# TrafficLight_ABCDEF.net
KiCad netlist of a schematic drawn in Altium Designer
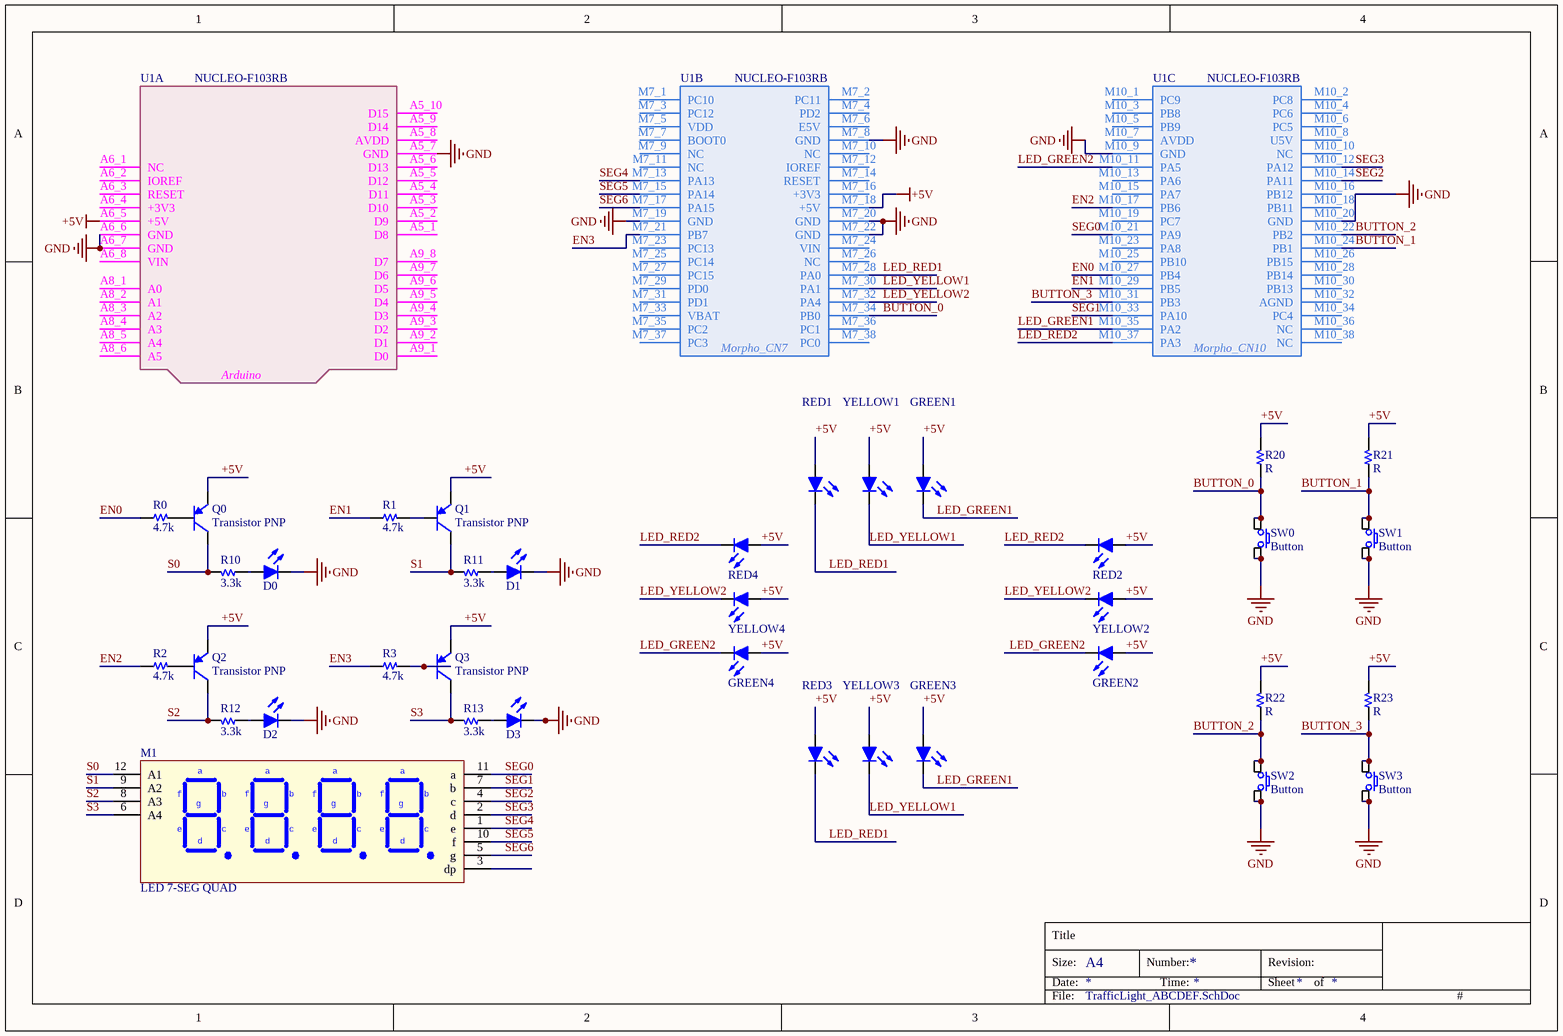
[diagram p0: TrafficLight_ABCDEF.SchDoc]

(export (version "E")
  (design (tool "Eeschema 10.0.6"))
  (components
    (comp (ref "D0")
      (value "Led")
      (footprint "Led 0603 - red")
      (description "Typical LED")
      (libsource (lib "led") (part "Led"))
    )
    (comp (ref "D1")
      (value "Led")
      (footprint "Led 0603 - red")
      (description "Typical LED")
      (libsource (lib "led") (part "Led"))
    )
    (comp (ref "D2")
      (value "Led")
      (footprint "Led 0603 - red")
      (description "Typical LED")
      (libsource (lib "led") (part "Led"))
    )
    (comp (ref "D3")
      (value "Led")
      (footprint "Led 0603 - red")
      (description "Typical LED")
      (libsource (lib "led") (part "Led"))
    )
    (comp (ref "GREEN1")
      (value "Led")
      (footprint "LED 5MM - GREEN")
      (description "Typical LED")
      (libsource (lib "led") (part "Led"))
    )
    (comp (ref "GREEN2")
      (value "Led")
      (footprint "LED 5MM - GREEN")
      (description "Typical LED")
      (libsource (lib "led") (part "Led"))
    )
    (comp (ref "GREEN3")
      (value "Led")
      (footprint "LED 5MM - GREEN")
      (description "Typical LED")
      (libsource (lib "led") (part "Led"))
    )
    (comp (ref "GREEN4")
      (value "Led")
      (footprint "LED 5MM - GREEN")
      (description "Typical LED")
      (libsource (lib "led") (part "Led"))
    )
    (comp (ref "M1")
      (value "LED 7-SEG QUAD")
      (footprint "LED/7SEG/0.56/QUAD")
      (description "LED 7-SEG 0.56 QUAD RED")
      (libsource (lib "led") (part "LED 7-SEG QUAD"))
    )
    (comp (ref "Q0")
      (value "Transistor PNP")
      (footprint "SOT-23")
      (description "PNP Bipolar Transistor")
      (libsource (lib "chipfc_libs") (part "Transistor PNP"))
    )
    (comp (ref "Q1")
      (value "Transistor PNP")
      (footprint "SOT-23")
      (description "PNP Bipolar Transistor")
      (libsource (lib "chipfc_libs") (part "Transistor PNP"))
    )
    (comp (ref "Q2")
      (value "Transistor PNP")
      (footprint "SOT-23")
      (description "PNP Bipolar Transistor")
      (libsource (lib "chipfc_libs") (part "Transistor PNP"))
    )
    (comp (ref "Q3")
      (value "Transistor PNP")
      (footprint "SOT-23")
      (description "PNP Bipolar Transistor")
      (libsource (lib "chipfc_libs") (part "Transistor PNP"))
    )
    (comp (ref "R0")
      (value "4.7k")
      (footprint "R 0805")
      (description "Resistor")
      (libsource (lib "chipfc_libs") (part "Resistor"))
    )
    (comp (ref "R1")
      (value "4.7k")
      (footprint "R 0805")
      (description "Resistor")
      (libsource (lib "chipfc_libs") (part "Resistor"))
    )
    (comp (ref "R2")
      (value "4.7k")
      (footprint "R 0805")
      (description "Resistor")
      (libsource (lib "chipfc_libs") (part "Resistor"))
    )
    (comp (ref "R3")
      (value "4.7k")
      (footprint "R 0805")
      (description "Resistor")
      (libsource (lib "chipfc_libs") (part "Resistor"))
    )
    (comp (ref "R10")
      (value "3.3k")
      (footprint "R 0805")
      (description "Resistor")
      (libsource (lib "chipfc_libs") (part "Resistor"))
    )
    (comp (ref "R11")
      (value "3.3k")
      (footprint "R 0805")
      (description "Resistor")
      (libsource (lib "chipfc_libs") (part "Resistor"))
    )
    (comp (ref "R12")
      (value "3.3k")
      (footprint "R 0805")
      (description "Resistor")
      (libsource (lib "chipfc_libs") (part "Resistor"))
    )
    (comp (ref "R13")
      (value "3.3k")
      (footprint "R 0805")
      (description "Resistor")
      (libsource (lib "chipfc_libs") (part "Resistor"))
    )
    (comp (ref "R20")
      (value "R")
      (footprint "R 0805")
      (description "Resistor")
      (libsource (lib "chipfc_libs") (part "Resistor"))
    )
    (comp (ref "R21")
      (value "R")
      (footprint "R 0805")
      (description "Resistor")
      (libsource (lib "chipfc_libs") (part "Resistor"))
    )
    (comp (ref "R22")
      (value "R")
      (footprint "R 0805")
      (description "Resistor")
      (libsource (lib "chipfc_libs") (part "Resistor"))
    )
    (comp (ref "R23")
      (value "R")
      (footprint "R 0805")
      (description "Resistor")
      (libsource (lib "chipfc_libs") (part "Resistor"))
    )
    (comp (ref "RED1")
      (value "Led")
      (footprint "LED 3MM - red")
      (description "Typical LED")
      (libsource (lib "led") (part "Led"))
    )
    (comp (ref "RED2")
      (value "Led")
      (footprint "LED 3MM - red")
      (description "Typical LED")
      (libsource (lib "led") (part "Led"))
    )
    (comp (ref "RED3")
      (value "Led")
      (footprint "LED 3MM - red")
      (description "Typical LED")
      (libsource (lib "led") (part "Led"))
    )
    (comp (ref "RED4")
      (value "Led")
      (footprint "LED 3MM - red")
      (description "Typical LED")
      (libsource (lib "led") (part "Led"))
    )
    (comp (ref "SW0")
      (value "Button")
      (footprint "SW/4/12mm")
      (description "Tact switch 4-pin")
      (libsource (lib "bs_libs") (part "SW SPST 4-pin"))
    )
    (comp (ref "SW1")
      (value "Button")
      (footprint "SW/4/12mm")
      (description "Tact switch 4-pin")
      (libsource (lib "bs_libs") (part "SW SPST 4-pin"))
    )
    (comp (ref "SW2")
      (value "Button")
      (footprint "SW/4/12mm")
      (description "Tact switch 4-pin")
      (libsource (lib "bs_libs") (part "SW SPST 4-pin"))
    )
    (comp (ref "SW3")
      (value "Button")
      (footprint "SW/4/12mm")
      (description "Tact switch 4-pin")
      (libsource (lib "bs_libs") (part "SW SPST 4-pin"))
    )
    (comp (ref "U1")
      (value "NUCLEO-F103RB")
      (footprint "NUCLEO")
      (fields (field (name "MANUFACTURER") "STMicroelectronics"))
      (libsource (lib "nucleo") (part "NUCLEO-F103RB"))
    )
    (comp (ref "YELLOW1")
      (value "Led")
      (footprint "LED 3MM - yellow")
      (description "Typical LED")
      (libsource (lib "led") (part "Led"))
    )
    (comp (ref "YELLOW2")
      (value "Led")
      (footprint "LED 3MM - yellow")
      (description "Typical LED")
      (libsource (lib "led") (part "Led"))
    )
    (comp (ref "YELLOW3")
      (value "Led")
      (footprint "LED 3MM - yellow")
      (description "Typical LED")
      (libsource (lib "led") (part "Led"))
    )
    (comp (ref "YELLOW4")
      (value "Led")
      (footprint "LED 3MM - yellow")
      (description "Typical LED")
      (libsource (lib "led") (part "Led"))
    )
  )
  (nets
    (net (code "1") (name "+5V") (class "Default")
      (node (ref "GREEN1") (pin "1") (pinfunction "A_1") (pintype "passive"))
      (node (ref "GREEN2") (pin "1") (pinfunction "A_1") (pintype "passive"))
      (node (ref "GREEN3") (pin "1") (pinfunction "A_1") (pintype "passive"))
      (node (ref "GREEN4") (pin "1") (pinfunction "A_1") (pintype "passive"))
      (node (ref "Q0") (pin "2") (pinfunction "E_2") (pintype "passive"))
      (node (ref "Q1") (pin "2") (pinfunction "E_2") (pintype "passive"))
      (node (ref "Q2") (pin "2") (pinfunction "E_2") (pintype "passive"))
      (node (ref "Q3") (pin "2") (pinfunction "E_2") (pintype "passive"))
      (node (ref "R20") (pin "2") (pinfunction "2_2") (pintype "passive"))
      (node (ref "R21") (pin "2") (pinfunction "2_2") (pintype "passive"))
      (node (ref "R22") (pin "2") (pinfunction "2_2") (pintype "passive"))
      (node (ref "R23") (pin "2") (pinfunction "2_2") (pintype "passive"))
      (node (ref "RED1") (pin "1") (pinfunction "A_1") (pintype "passive"))
      (node (ref "RED2") (pin "1") (pinfunction "A_1") (pintype "passive"))
      (node (ref "RED3") (pin "1") (pinfunction "A_1") (pintype "passive"))
      (node (ref "RED4") (pin "1") (pinfunction "A_1") (pintype "passive"))
      (node (ref "U1") (pin "A6_5") (pinfunction "+5V_A6_5") (pintype "passive"))
      (node (ref "U1") (pin "M7_18") (pinfunction "+5V_M7_18") (pintype "passive"))
      (node (ref "YELLOW1") (pin "1") (pinfunction "A_1") (pintype "passive"))
      (node (ref "YELLOW2") (pin "1") (pinfunction "A_1") (pintype "passive"))
      (node (ref "YELLOW3") (pin "1") (pinfunction "A_1") (pintype "passive"))
      (node (ref "YELLOW4") (pin "1") (pinfunction "A_1") (pintype "passive"))
    )
    (net (code "2") (name "/BUTTON_0") (class "Default")
      (node (ref "R20") (pin "1") (pinfunction "1_1") (pintype "passive"))
      (node (ref "SW0") (pin "1") (pinfunction "1_1") (pintype "passive"))
      (node (ref "SW0") (pin "2") (pinfunction "2_2") (pintype "passive"))
      (node (ref "U1") (pin "M7_34") (pinfunction "PB0_M7_34") (pintype "passive"))
    )
    (net (code "3") (name "/BUTTON_1") (class "Default")
      (node (ref "R21") (pin "1") (pinfunction "1_1") (pintype "passive"))
      (node (ref "SW1") (pin "1") (pinfunction "1_1") (pintype "passive"))
      (node (ref "SW1") (pin "2") (pinfunction "2_2") (pintype "passive"))
      (node (ref "U1") (pin "M10_24") (pinfunction "PB1_M10_24") (pintype "passive"))
    )
    (net (code "4") (name "/BUTTON_2") (class "Default")
      (node (ref "R22") (pin "1") (pinfunction "1_1") (pintype "passive"))
      (node (ref "SW2") (pin "1") (pinfunction "1_1") (pintype "passive"))
      (node (ref "SW2") (pin "2") (pinfunction "2_2") (pintype "passive"))
      (node (ref "U1") (pin "M10_22") (pinfunction "PB2_M10_22") (pintype "passive"))
    )
    (net (code "5") (name "/BUTTON_3") (class "Default")
      (node (ref "R23") (pin "1") (pinfunction "1_1") (pintype "passive"))
      (node (ref "SW3") (pin "1") (pinfunction "1_1") (pintype "passive"))
      (node (ref "SW3") (pin "2") (pinfunction "2_2") (pintype "passive"))
      (node (ref "U1") (pin "M10_31") (pinfunction "PB3_M10_31") (pintype "passive"))
    )
    (net (code "6") (name "/EN0") (class "Default")
      (node (ref "R0") (pin "1") (pinfunction "1_1") (pintype "passive"))
      (node (ref "U1") (pin "M10_27") (pinfunction "PB4_M10_27") (pintype "passive"))
    )
    (net (code "7") (name "/EN1") (class "Default")
      (node (ref "R1") (pin "1") (pinfunction "1_1") (pintype "passive"))
      (node (ref "U1") (pin "M10_29") (pinfunction "PB5_M10_29") (pintype "passive"))
    )
    (net (code "8") (name "/EN2") (class "Default")
      (node (ref "R2") (pin "1") (pinfunction "1_1") (pintype "passive"))
      (node (ref "U1") (pin "M10_17") (pinfunction "PB6_M10_17") (pintype "passive"))
    )
    (net (code "9") (name "/EN3") (class "Default")
      (node (ref "R3") (pin "1") (pinfunction "1_1") (pintype "passive"))
      (node (ref "U1") (pin "M7_21") (pinfunction "PB7_M7_21") (pintype "passive"))
    )
    (net (code "10") (name "/LED_GREEN1") (class "Default")
      (node (ref "GREEN1") (pin "2") (pinfunction "K_2") (pintype "passive"))
      (node (ref "GREEN3") (pin "2") (pinfunction "K_2") (pintype "passive"))
      (node (ref "U1") (pin "M10_35") (pinfunction "PA2_M10_35") (pintype "passive"))
    )
    (net (code "11") (name "/LED_GREEN2") (class "Default")
      (node (ref "GREEN2") (pin "2") (pinfunction "K_2") (pintype "passive"))
      (node (ref "GREEN4") (pin "2") (pinfunction "K_2") (pintype "passive"))
      (node (ref "U1") (pin "M10_11") (pinfunction "PA5_M10_11") (pintype "passive"))
    )
    (net (code "12") (name "/LED_RED1") (class "Default")
      (node (ref "RED1") (pin "2") (pinfunction "K_2") (pintype "passive"))
      (node (ref "RED3") (pin "2") (pinfunction "K_2") (pintype "passive"))
      (node (ref "U1") (pin "M7_28") (pinfunction "PA0_M7_28") (pintype "passive"))
    )
    (net (code "13") (name "/LED_RED2") (class "Default")
      (node (ref "RED2") (pin "2") (pinfunction "K_2") (pintype "passive"))
      (node (ref "RED4") (pin "2") (pinfunction "K_2") (pintype "passive"))
      (node (ref "U1") (pin "M10_37") (pinfunction "PA3_M10_37") (pintype "passive"))
    )
    (net (code "14") (name "/LED_YELLOW1") (class "Default")
      (node (ref "U1") (pin "M7_30") (pinfunction "PA1_M7_30") (pintype "passive"))
      (node (ref "YELLOW1") (pin "2") (pinfunction "K_2") (pintype "passive"))
      (node (ref "YELLOW3") (pin "2") (pinfunction "K_2") (pintype "passive"))
    )
    (net (code "15") (name "/LED_YELLOW2") (class "Default")
      (node (ref "U1") (pin "M7_32") (pinfunction "PA4_M7_32") (pintype "passive"))
      (node (ref "YELLOW2") (pin "2") (pinfunction "K_2") (pintype "passive"))
      (node (ref "YELLOW4") (pin "2") (pinfunction "K_2") (pintype "passive"))
    )
    (net (code "16") (name "/S0") (class "Default")
      (node (ref "M1") (pin "12") (pinfunction "A1_12") (pintype "passive"))
      (node (ref "Q0") (pin "3") (pinfunction "C_3") (pintype "passive"))
      (node (ref "R10") (pin "2") (pinfunction "2_2") (pintype "passive"))
    )
    (net (code "17") (name "/S1") (class "Default")
      (node (ref "M1") (pin "9") (pinfunction "A2_9") (pintype "passive"))
      (node (ref "Q1") (pin "3") (pinfunction "C_3") (pintype "passive"))
      (node (ref "R11") (pin "2") (pinfunction "2_2") (pintype "passive"))
    )
    (net (code "18") (name "/S2") (class "Default")
      (node (ref "M1") (pin "8") (pinfunction "A3_8") (pintype "passive"))
      (node (ref "Q2") (pin "3") (pinfunction "C_3") (pintype "passive"))
      (node (ref "R12") (pin "2") (pinfunction "2_2") (pintype "passive"))
    )
    (net (code "19") (name "/S3") (class "Default")
      (node (ref "M1") (pin "6") (pinfunction "A4_6") (pintype "passive"))
      (node (ref "Q3") (pin "3") (pinfunction "C_3") (pintype "passive"))
      (node (ref "R13") (pin "2") (pinfunction "2_2") (pintype "passive"))
    )
    (net (code "20") (name "/SEG0") (class "Default")
      (node (ref "M1") (pin "11") (pinfunction "a_11") (pintype "passive"))
      (node (ref "U1") (pin "M10_21") (pinfunction "PA9_M10_21") (pintype "passive"))
    )
    (net (code "21") (name "/SEG1") (class "Default")
      (node (ref "M1") (pin "7") (pinfunction "b_7") (pintype "passive"))
      (node (ref "U1") (pin "M10_33") (pinfunction "PA10_M10_33") (pintype "passive"))
    )
    (net (code "22") (name "/SEG2") (class "Default")
      (node (ref "M1") (pin "4") (pinfunction "c_4") (pintype "passive"))
      (node (ref "U1") (pin "M10_14") (pinfunction "PA11_M10_14") (pintype "passive"))
    )
    (net (code "23") (name "/SEG3") (class "Default")
      (node (ref "M1") (pin "2") (pinfunction "d_2") (pintype "passive"))
      (node (ref "U1") (pin "M10_12") (pinfunction "PA12_M10_12") (pintype "passive"))
    )
    (net (code "24") (name "/SEG4") (class "Default")
      (node (ref "M1") (pin "1") (pinfunction "e_1") (pintype "passive"))
      (node (ref "U1") (pin "M7_13") (pinfunction "PA13_M7_13") (pintype "passive"))
    )
    (net (code "25") (name "/SEG5") (class "Default")
      (node (ref "M1") (pin "10") (pinfunction "f_10") (pintype "passive"))
      (node (ref "U1") (pin "M7_15") (pinfunction "PA14_M7_15") (pintype "passive"))
    )
    (net (code "26") (name "/SEG6") (class "Default")
      (node (ref "M1") (pin "5") (pinfunction "g_5") (pintype "passive"))
      (node (ref "U1") (pin "M7_17") (pinfunction "PA15_M7_17") (pintype "passive"))
    )
    (net (code "27") (name "GND") (class "Default")
      (node (ref "D0") (pin "2") (pinfunction "K_2") (pintype "passive"))
      (node (ref "D1") (pin "2") (pinfunction "K_2") (pintype "passive"))
      (node (ref "D2") (pin "2") (pinfunction "K_2") (pintype "passive"))
      (node (ref "D3") (pin "2") (pinfunction "K_2") (pintype "passive"))
      (node (ref "SW0") (pin "3") (pinfunction "3_3") (pintype "passive"))
      (node (ref "SW0") (pin "4") (pinfunction "4_4") (pintype "passive"))
      (node (ref "SW1") (pin "3") (pinfunction "3_3") (pintype "passive"))
      (node (ref "SW1") (pin "4") (pinfunction "4_4") (pintype "passive"))
      (node (ref "SW2") (pin "3") (pinfunction "3_3") (pintype "passive"))
      (node (ref "SW2") (pin "4") (pinfunction "4_4") (pintype "passive"))
      (node (ref "SW3") (pin "3") (pinfunction "3_3") (pintype "passive"))
      (node (ref "SW3") (pin "4") (pinfunction "4_4") (pintype "passive"))
      (node (ref "U1") (pin "A5_7") (pinfunction "GND_A5_7") (pintype "passive"))
      (node (ref "U1") (pin "A6_6") (pinfunction "GND_A6_6") (pintype "passive"))
      (node (ref "U1") (pin "A6_7") (pinfunction "GND_A6_7") (pintype "passive"))
      (node (ref "U1") (pin "M10_20") (pinfunction "GND_M10_20") (pintype "passive"))
      (node (ref "U1") (pin "M10_9") (pinfunction "GND_M10_9") (pintype "passive"))
      (node (ref "U1") (pin "M7_19") (pinfunction "GND_M7_19") (pintype "passive"))
      (node (ref "U1") (pin "M7_20") (pinfunction "GND_M7_20") (pintype "passive"))
      (node (ref "U1") (pin "M7_22") (pinfunction "GND_M7_22") (pintype "passive"))
      (node (ref "U1") (pin "M7_8") (pinfunction "GND_M7_8") (pintype "passive"))
    )
    (net (code "28") (name "Net-(D0-A)") (class "Default")
      (node (ref "D0") (pin "1") (pinfunction "A_1") (pintype "passive"))
      (node (ref "R10") (pin "1") (pinfunction "1_1") (pintype "passive"))
    )
    (net (code "29") (name "Net-(D1-A)") (class "Default")
      (node (ref "D1") (pin "1") (pinfunction "A_1") (pintype "passive"))
      (node (ref "R11") (pin "1") (pinfunction "1_1") (pintype "passive"))
    )
    (net (code "30") (name "Net-(D2-A)") (class "Default")
      (node (ref "D2") (pin "1") (pinfunction "A_1") (pintype "passive"))
      (node (ref "R12") (pin "1") (pinfunction "1_1") (pintype "passive"))
    )
    (net (code "31") (name "Net-(D3-A)") (class "Default")
      (node (ref "D3") (pin "1") (pinfunction "A_1") (pintype "passive"))
      (node (ref "R13") (pin "1") (pinfunction "1_1") (pintype "passive"))
    )
    (net (code "32") (name "Net-(Q0-B)") (class "Default")
      (node (ref "Q0") (pin "1") (pinfunction "B_1") (pintype "passive"))
      (node (ref "R0") (pin "2") (pinfunction "2_2") (pintype "passive"))
    )
    (net (code "33") (name "Net-(Q1-B)") (class "Default")
      (node (ref "Q1") (pin "1") (pinfunction "B_1") (pintype "passive"))
      (node (ref "R1") (pin "2") (pinfunction "2_2") (pintype "passive"))
    )
    (net (code "34") (name "Net-(Q2-B)") (class "Default")
      (node (ref "Q2") (pin "1") (pinfunction "B_1") (pintype "passive"))
      (node (ref "R2") (pin "2") (pinfunction "2_2") (pintype "passive"))
    )
    (net (code "35") (name "Net-(Q3-B)") (class "Default")
      (node (ref "Q3") (pin "1") (pinfunction "B_1") (pintype "passive"))
      (node (ref "R3") (pin "2") (pinfunction "2_2") (pintype "passive"))
    )
    (net (code "36") (name "unconnected-(M1-dp-Pad3)") (class "Default")
      (node (ref "M1") (pin "3") (pinfunction "dp_3") (pintype "passive"))
    )
    (net (code "37") (name "unconnected-(U1A-+3V3-PadA6_4)") (class "Default")
      (node (ref "U1") (pin "A6_4") (pinfunction "+3V3_A6_4") (pintype "passive"))
    )
    (net (code "38") (name "unconnected-(U1A-A0-PadA8_1)") (class "Default")
      (node (ref "U1") (pin "A8_1") (pinfunction "A0_A8_1") (pintype "passive"))
    )
    (net (code "39") (name "unconnected-(U1A-A1-PadA8_2)") (class "Default")
      (node (ref "U1") (pin "A8_2") (pinfunction "A1_A8_2") (pintype "passive"))
    )
    (net (code "40") (name "unconnected-(U1A-A2-PadA8_3)") (class "Default")
      (node (ref "U1") (pin "A8_3") (pinfunction "A2_A8_3") (pintype "passive"))
    )
    (net (code "41") (name "unconnected-(U1A-A3-PadA8_4)") (class "Default")
      (node (ref "U1") (pin "A8_4") (pinfunction "A3_A8_4") (pintype "passive"))
    )
    (net (code "42") (name "unconnected-(U1A-A4-PadA8_5)") (class "Default")
      (node (ref "U1") (pin "A8_5") (pinfunction "A4_A8_5") (pintype "passive"))
    )
    (net (code "43") (name "unconnected-(U1A-A5-PadA8_6)") (class "Default")
      (node (ref "U1") (pin "A8_6") (pinfunction "A5_A8_6") (pintype "passive"))
    )
    (net (code "44") (name "unconnected-(U1A-AVDD-PadA5_8)") (class "Default")
      (node (ref "U1") (pin "A5_8") (pinfunction "AVDD_A5_8") (pintype "passive"))
    )
    (net (code "45") (name "unconnected-(U1A-D0-PadA9_1)") (class "Default")
      (node (ref "U1") (pin "A9_1") (pinfunction "D0_A9_1") (pintype "passive"))
    )
    (net (code "46") (name "unconnected-(U1A-D1-PadA9_2)") (class "Default")
      (node (ref "U1") (pin "A9_2") (pinfunction "D1_A9_2") (pintype "passive"))
    )
    (net (code "47") (name "unconnected-(U1A-D2-PadA9_3)") (class "Default")
      (node (ref "U1") (pin "A9_3") (pinfunction "D2_A9_3") (pintype "passive"))
    )
    (net (code "48") (name "unconnected-(U1A-D3-PadA9_4)") (class "Default")
      (node (ref "U1") (pin "A9_4") (pinfunction "D3_A9_4") (pintype "passive"))
    )
    (net (code "49") (name "unconnected-(U1A-D4-PadA9_5)") (class "Default")
      (node (ref "U1") (pin "A9_5") (pinfunction "D4_A9_5") (pintype "passive"))
    )
    (net (code "50") (name "unconnected-(U1A-D5-PadA9_6)") (class "Default")
      (node (ref "U1") (pin "A9_6") (pinfunction "D5_A9_6") (pintype "passive"))
    )
    (net (code "51") (name "unconnected-(U1A-D6-PadA9_7)") (class "Default")
      (node (ref "U1") (pin "A9_7") (pinfunction "D6_A9_7") (pintype "passive"))
    )
    (net (code "52") (name "unconnected-(U1A-D7-PadA9_8)") (class "Default")
      (node (ref "U1") (pin "A9_8") (pinfunction "D7_A9_8") (pintype "passive"))
    )
    (net (code "53") (name "unconnected-(U1A-D8-PadA5_1)") (class "Default")
      (node (ref "U1") (pin "A5_1") (pinfunction "D8_A5_1") (pintype "passive"))
    )
    (net (code "54") (name "unconnected-(U1A-D9-PadA5_2)") (class "Default")
      (node (ref "U1") (pin "A5_2") (pinfunction "D9_A5_2") (pintype "passive"))
    )
    (net (code "55") (name "unconnected-(U1A-D10-PadA5_3)") (class "Default")
      (node (ref "U1") (pin "A5_3") (pinfunction "D10_A5_3") (pintype "passive"))
    )
    (net (code "56") (name "unconnected-(U1A-D11-PadA5_4)") (class "Default")
      (node (ref "U1") (pin "A5_4") (pinfunction "D11_A5_4") (pintype "passive"))
    )
    (net (code "57") (name "unconnected-(U1A-D12-PadA5_5)") (class "Default")
      (node (ref "U1") (pin "A5_5") (pinfunction "D12_A5_5") (pintype "passive"))
    )
    (net (code "58") (name "unconnected-(U1A-D13-PadA5_6)") (class "Default")
      (node (ref "U1") (pin "A5_6") (pinfunction "D13_A5_6") (pintype "passive"))
    )
    (net (code "59") (name "unconnected-(U1A-D14-PadA5_9)") (class "Default")
      (node (ref "U1") (pin "A5_9") (pinfunction "D14_A5_9") (pintype "passive"))
    )
    (net (code "60") (name "unconnected-(U1A-D15-PadA5_10)") (class "Default")
      (node (ref "U1") (pin "A5_10") (pinfunction "D15_A5_10") (pintype "passive"))
    )
    (net (code "61") (name "unconnected-(U1A-IOREF-PadA6_2)") (class "Default")
      (node (ref "U1") (pin "A6_2") (pinfunction "IOREF_A6_2") (pintype "passive"))
    )
    (net (code "62") (name "unconnected-(U1A-NC-PadA6_1)") (class "Default")
      (node (ref "U1") (pin "A6_1") (pinfunction "NC_A6_1") (pintype "passive"))
    )
    (net (code "63") (name "unconnected-(U1A-RESET-PadA6_3)") (class "Default")
      (node (ref "U1") (pin "A6_3") (pinfunction "RESET_A6_3") (pintype "passive"))
    )
    (net (code "64") (name "unconnected-(U1A-VIN-PadA6_8)") (class "Default")
      (node (ref "U1") (pin "A6_8") (pinfunction "VIN_A6_8") (pintype "passive"))
    )
    (net (code "65") (name "unconnected-(U1B-+3V3-PadM7_16)") (class "Default")
      (node (ref "U1") (pin "M7_16") (pinfunction "+3V3_M7_16") (pintype "passive"))
    )
    (net (code "66") (name "unconnected-(U1B-BOOT0-PadM7_7)") (class "Default")
      (node (ref "U1") (pin "M7_7") (pinfunction "BOOT0_M7_7") (pintype "passive"))
    )
    (net (code "67") (name "unconnected-(U1B-E5V-PadM7_6)") (class "Default")
      (node (ref "U1") (pin "M7_6") (pinfunction "E5V_M7_6") (pintype "passive"))
    )
    (net (code "68") (name "unconnected-(U1B-IOREF-PadM7_12)") (class "Default")
      (node (ref "U1") (pin "M7_12") (pinfunction "IOREF_M7_12") (pintype "passive"))
    )
    (net (code "69") (name "unconnected-(U1B-NC-PadM7_9)") (class "Default")
      (node (ref "U1") (pin "M7_9") (pinfunction "NC_M7_9") (pintype "passive"))
    )
    (net (code "70") (name "unconnected-(U1B-NC-PadM7_10)") (class "Default")
      (node (ref "U1") (pin "M7_10") (pinfunction "NC_M7_10") (pintype "passive"))
    )
    (net (code "71") (name "unconnected-(U1B-NC-PadM7_11)") (class "Default")
      (node (ref "U1") (pin "M7_11") (pinfunction "NC_M7_11") (pintype "passive"))
    )
    (net (code "72") (name "unconnected-(U1B-NC-PadM7_26)") (class "Default")
      (node (ref "U1") (pin "M7_26") (pinfunction "NC_M7_26") (pintype "passive"))
    )
    (net (code "73") (name "unconnected-(U1B-PC0-PadM7_38)") (class "Default")
      (node (ref "U1") (pin "M7_38") (pinfunction "PC0_M7_38") (pintype "passive"))
    )
    (net (code "74") (name "unconnected-(U1B-PC1-PadM7_36)") (class "Default")
      (node (ref "U1") (pin "M7_36") (pinfunction "PC1_M7_36") (pintype "passive"))
    )
    (net (code "75") (name "unconnected-(U1B-PC2-PadM7_35)") (class "Default")
      (node (ref "U1") (pin "M7_35") (pinfunction "PC2_M7_35") (pintype "passive"))
    )
    (net (code "76") (name "unconnected-(U1B-PC3-PadM7_37)") (class "Default")
      (node (ref "U1") (pin "M7_37") (pinfunction "PC3_M7_37") (pintype "passive"))
    )
    (net (code "77") (name "unconnected-(U1B-PC10-PadM7_1)") (class "Default")
      (node (ref "U1") (pin "M7_1") (pinfunction "PC10_M7_1") (pintype "passive"))
    )
    (net (code "78") (name "unconnected-(U1B-PC11-PadM7_2)") (class "Default")
      (node (ref "U1") (pin "M7_2") (pinfunction "PC11_M7_2") (pintype "passive"))
    )
    (net (code "79") (name "unconnected-(U1B-PC12-PadM7_3)") (class "Default")
      (node (ref "U1") (pin "M7_3") (pinfunction "PC12_M7_3") (pintype "passive"))
    )
    (net (code "80") (name "unconnected-(U1B-PC13-PadM7_23)") (class "Default")
      (node (ref "U1") (pin "M7_23") (pinfunction "PC13_M7_23") (pintype "passive"))
    )
    (net (code "81") (name "unconnected-(U1B-PC14-PadM7_25)") (class "Default")
      (node (ref "U1") (pin "M7_25") (pinfunction "PC14_M7_25") (pintype "passive"))
    )
    (net (code "82") (name "unconnected-(U1B-PC15-PadM7_27)") (class "Default")
      (node (ref "U1") (pin "M7_27") (pinfunction "PC15_M7_27") (pintype "passive"))
    )
    (net (code "83") (name "unconnected-(U1B-PD0-PadM7_29)") (class "Default")
      (node (ref "U1") (pin "M7_29") (pinfunction "PD0_M7_29") (pintype "passive"))
    )
    (net (code "84") (name "unconnected-(U1B-PD1-PadM7_31)") (class "Default")
      (node (ref "U1") (pin "M7_31") (pinfunction "PD1_M7_31") (pintype "passive"))
    )
    (net (code "85") (name "unconnected-(U1B-PD2-PadM7_4)") (class "Default")
      (node (ref "U1") (pin "M7_4") (pinfunction "PD2_M7_4") (pintype "passive"))
    )
    (net (code "86") (name "unconnected-(U1B-RESET-PadM7_14)") (class "Default")
      (node (ref "U1") (pin "M7_14") (pinfunction "RESET_M7_14") (pintype "passive"))
    )
    (net (code "87") (name "unconnected-(U1B-VBAT-PadM7_33)") (class "Default")
      (node (ref "U1") (pin "M7_33") (pinfunction "VBAT_M7_33") (pintype "passive"))
    )
    (net (code "88") (name "unconnected-(U1B-VDD-PadM7_5)") (class "Default")
      (node (ref "U1") (pin "M7_5") (pinfunction "VDD_M7_5") (pintype "passive"))
    )
    (net (code "89") (name "unconnected-(U1B-VIN-PadM7_24)") (class "Default")
      (node (ref "U1") (pin "M7_24") (pinfunction "VIN_M7_24") (pintype "passive"))
    )
    (net (code "90") (name "unconnected-(U1C-AGND-PadM10_32)") (class "Default")
      (node (ref "U1") (pin "M10_32") (pinfunction "AGND_M10_32") (pintype "passive"))
    )
    (net (code "91") (name "unconnected-(U1C-AVDD-PadM10_7)") (class "Default")
      (node (ref "U1") (pin "M10_7") (pinfunction "AVDD_M10_7") (pintype "passive"))
    )
    (net (code "92") (name "unconnected-(U1C-NC-PadM10_10)") (class "Default")
      (node (ref "U1") (pin "M10_10") (pinfunction "NC_M10_10") (pintype "passive"))
    )
    (net (code "93") (name "unconnected-(U1C-NC-PadM10_36)") (class "Default")
      (node (ref "U1") (pin "M10_36") (pinfunction "NC_M10_36") (pintype "passive"))
    )
    (net (code "94") (name "unconnected-(U1C-NC-PadM10_38)") (class "Default")
      (node (ref "U1") (pin "M10_38") (pinfunction "NC_M10_38") (pintype "passive"))
    )
    (net (code "95") (name "unconnected-(U1C-PA6-PadM10_13)") (class "Default")
      (node (ref "U1") (pin "M10_13") (pinfunction "PA6_M10_13") (pintype "passive"))
    )
    (net (code "96") (name "unconnected-(U1C-PA7-PadM10_15)") (class "Default")
      (node (ref "U1") (pin "M10_15") (pinfunction "PA7_M10_15") (pintype "passive"))
    )
    (net (code "97") (name "unconnected-(U1C-PA8-PadM10_23)") (class "Default")
      (node (ref "U1") (pin "M10_23") (pinfunction "PA8_M10_23") (pintype "passive"))
    )
    (net (code "98") (name "unconnected-(U1C-PB8-PadM10_3)") (class "Default")
      (node (ref "U1") (pin "M10_3") (pinfunction "PB8_M10_3") (pintype "passive"))
    )
    (net (code "99") (name "unconnected-(U1C-PB9-PadM10_5)") (class "Default")
      (node (ref "U1") (pin "M10_5") (pinfunction "PB9_M10_5") (pintype "passive"))
    )
    (net (code "100") (name "unconnected-(U1C-PB10-PadM10_25)") (class "Default")
      (node (ref "U1") (pin "M10_25") (pinfunction "PB10_M10_25") (pintype "passive"))
    )
    (net (code "101") (name "unconnected-(U1C-PB11-PadM10_18)") (class "Default")
      (node (ref "U1") (pin "M10_18") (pinfunction "PB11_M10_18") (pintype "passive"))
    )
    (net (code "102") (name "unconnected-(U1C-PB12-PadM10_16)") (class "Default")
      (node (ref "U1") (pin "M10_16") (pinfunction "PB12_M10_16") (pintype "passive"))
    )
    (net (code "103") (name "unconnected-(U1C-PB13-PadM10_30)") (class "Default")
      (node (ref "U1") (pin "M10_30") (pinfunction "PB13_M10_30") (pintype "passive"))
    )
    (net (code "104") (name "unconnected-(U1C-PB14-PadM10_28)") (class "Default")
      (node (ref "U1") (pin "M10_28") (pinfunction "PB14_M10_28") (pintype "passive"))
    )
    (net (code "105") (name "unconnected-(U1C-PB15-PadM10_26)") (class "Default")
      (node (ref "U1") (pin "M10_26") (pinfunction "PB15_M10_26") (pintype "passive"))
    )
    (net (code "106") (name "unconnected-(U1C-PC4-PadM10_34)") (class "Default")
      (node (ref "U1") (pin "M10_34") (pinfunction "PC4_M10_34") (pintype "passive"))
    )
    (net (code "107") (name "unconnected-(U1C-PC5-PadM10_6)") (class "Default")
      (node (ref "U1") (pin "M10_6") (pinfunction "PC5_M10_6") (pintype "passive"))
    )
    (net (code "108") (name "unconnected-(U1C-PC6-PadM10_4)") (class "Default")
      (node (ref "U1") (pin "M10_4") (pinfunction "PC6_M10_4") (pintype "passive"))
    )
    (net (code "109") (name "unconnected-(U1C-PC7-PadM10_19)") (class "Default")
      (node (ref "U1") (pin "M10_19") (pinfunction "PC7_M10_19") (pintype "passive"))
    )
    (net (code "110") (name "unconnected-(U1C-PC8-PadM10_2)") (class "Default")
      (node (ref "U1") (pin "M10_2") (pinfunction "PC8_M10_2") (pintype "passive"))
    )
    (net (code "111") (name "unconnected-(U1C-PC9-PadM10_1)") (class "Default")
      (node (ref "U1") (pin "M10_1") (pinfunction "PC9_M10_1") (pintype "passive"))
    )
    (net (code "112") (name "unconnected-(U1C-U5V-PadM10_8)") (class "Default")
      (node (ref "U1") (pin "M10_8") (pinfunction "U5V_M10_8") (pintype "passive"))
    )
  )
)
